# SCH1.net
KiCad netlist of a schematic drawn in Altium Designer
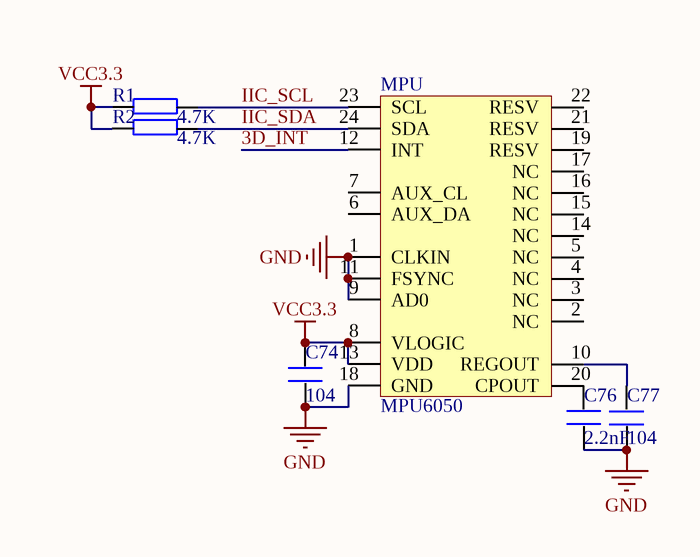
[diagram p0: SCH1.SchDoc]

(export (version "E")
  (design (tool "Eeschema 10.0.6"))
  (components
    (comp (ref "C74") (value "104") (footprint "C 0603_L") (libsource (lib "MYCOMLIB") (part "C")))
    (comp (ref "C76") (value "2.2nF") (footprint "C 0603_L") (libsource (lib "MYCOMLIB") (part "C")))
    (comp (ref "C77") (value "104") (footprint "C 0603_L") (libsource (lib "MYCOMLIB") (part "C")))
    (comp (ref "MPU")
      (value "MPU6050")
      (footprint "QFN24 4x4_N")
      (description "9轴运动处理传感器")
      (libsource (lib "ALIENTEK_COMPONENT") (part "MPU6050"))
    )
    (comp (ref "R1")
      (value "4.7K")
      (footprint "R 0603_L")
      (libsource (lib "WarShip V3 STM32103封装库") (part "R"))
    )
    (comp (ref "R2")
      (value "4.7K")
      (footprint "R 0603_L")
      (libsource (lib "WarShip V3 STM32103封装库") (part "R"))
    )
  )
  (nets
    (net (code "1") (name "/3D_INT") (class "Default")
      (node (ref "MPU") (pin "12") (pinfunction "INT_12") (pintype "passive"))
    )
    (net (code "2") (name "/IIC_SCL") (class "Default")
      (node (ref "MPU") (pin "23") (pinfunction "SCL_23") (pintype "passive"))
      (node (ref "R1") (pin "1") (pintype "passive"))
    )
    (net (code "3") (name "/IIC_SDA") (class "Default")
      (node (ref "MPU") (pin "24") (pinfunction "SDA_24") (pintype "passive"))
      (node (ref "R2") (pin "1") (pintype "passive"))
    )
    (net (code "4") (name "GND") (class "Default")
      (node (ref "C74") (pin "1") (pintype "passive"))
      (node (ref "C76") (pin "1") (pintype "passive"))
      (node (ref "C77") (pin "2") (pintype "passive"))
      (node (ref "MPU") (pin "1") (pinfunction "CLKIN_1") (pintype "passive"))
      (node (ref "MPU") (pin "11") (pinfunction "FSYNC_11") (pintype "passive"))
      (node (ref "MPU") (pin "18") (pinfunction "GND_18") (pintype "passive"))
      (node (ref "MPU") (pin "9") (pinfunction "AD0_9") (pintype "passive"))
    )
    (net (code "5") (name "Net-(MPU-CPOUT)") (class "Default")
      (node (ref "C76") (pin "2") (pintype "passive"))
      (node (ref "MPU") (pin "20") (pinfunction "CPOUT_20") (pintype "passive"))
    )
    (net (code "6") (name "Net-(MPU-REGOUT)") (class "Default")
      (node (ref "C77") (pin "1") (pintype "passive"))
      (node (ref "MPU") (pin "10") (pinfunction "REGOUT_10") (pintype "passive"))
    )
    (net (code "7") (name "VCC3.3") (class "Default")
      (node (ref "C74") (pin "2") (pintype "passive"))
      (node (ref "MPU") (pin "13") (pinfunction "VDD_13") (pintype "passive"))
      (node (ref "MPU") (pin "8") (pinfunction "VLOGIC_8") (pintype "passive"))
      (node (ref "R1") (pin "2") (pintype "passive"))
      (node (ref "R2") (pin "2") (pintype "passive"))
    )
    (net (code "8") (name "unconnected-(MPU-AUX_CL-Pad7)") (class "Default")
      (node (ref "MPU") (pin "7") (pinfunction "AUX_CL_7") (pintype "passive"))
    )
    (net (code "9") (name "unconnected-(MPU-AUX_DA-Pad6)") (class "Default")
      (node (ref "MPU") (pin "6") (pinfunction "AUX_DA_6") (pintype "passive"))
    )
    (net (code "10") (name "unconnected-(MPU-NC-Pad2)") (class "Default")
      (node (ref "MPU") (pin "2") (pinfunction "NC_2") (pintype "passive"))
    )
    (net (code "11") (name "unconnected-(MPU-NC-Pad3)") (class "Default")
      (node (ref "MPU") (pin "3") (pinfunction "NC_3") (pintype "passive"))
    )
    (net (code "12") (name "unconnected-(MPU-NC-Pad4)") (class "Default")
      (node (ref "MPU") (pin "4") (pinfunction "NC_4") (pintype "passive"))
    )
    (net (code "13") (name "unconnected-(MPU-NC-Pad5)") (class "Default")
      (node (ref "MPU") (pin "5") (pinfunction "NC_5") (pintype "passive"))
    )
    (net (code "14") (name "unconnected-(MPU-NC-Pad14)") (class "Default")
      (node (ref "MPU") (pin "14") (pinfunction "NC_14") (pintype "passive"))
    )
    (net (code "15") (name "unconnected-(MPU-NC-Pad15)") (class "Default")
      (node (ref "MPU") (pin "15") (pinfunction "NC_15") (pintype "passive"))
    )
    (net (code "16") (name "unconnected-(MPU-NC-Pad16)") (class "Default")
      (node (ref "MPU") (pin "16") (pinfunction "NC_16") (pintype "passive"))
    )
    (net (code "17") (name "unconnected-(MPU-NC-Pad17)") (class "Default")
      (node (ref "MPU") (pin "17") (pinfunction "NC_17") (pintype "passive"))
    )
    (net (code "18") (name "unconnected-(MPU-RESV-Pad19)") (class "Default")
      (node (ref "MPU") (pin "19") (pinfunction "RESV_19") (pintype "passive"))
    )
    (net (code "19") (name "unconnected-(MPU-RESV-Pad21)") (class "Default")
      (node (ref "MPU") (pin "21") (pinfunction "RESV_21") (pintype "passive"))
    )
    (net (code "20") (name "unconnected-(MPU-RESV-Pad22)") (class "Default")
      (node (ref "MPU") (pin "22") (pinfunction "RESV_22") (pintype "passive"))
    )
  )
)
